# controller_v1.net
KiCad netlist of a schematic drawn in EAGLE
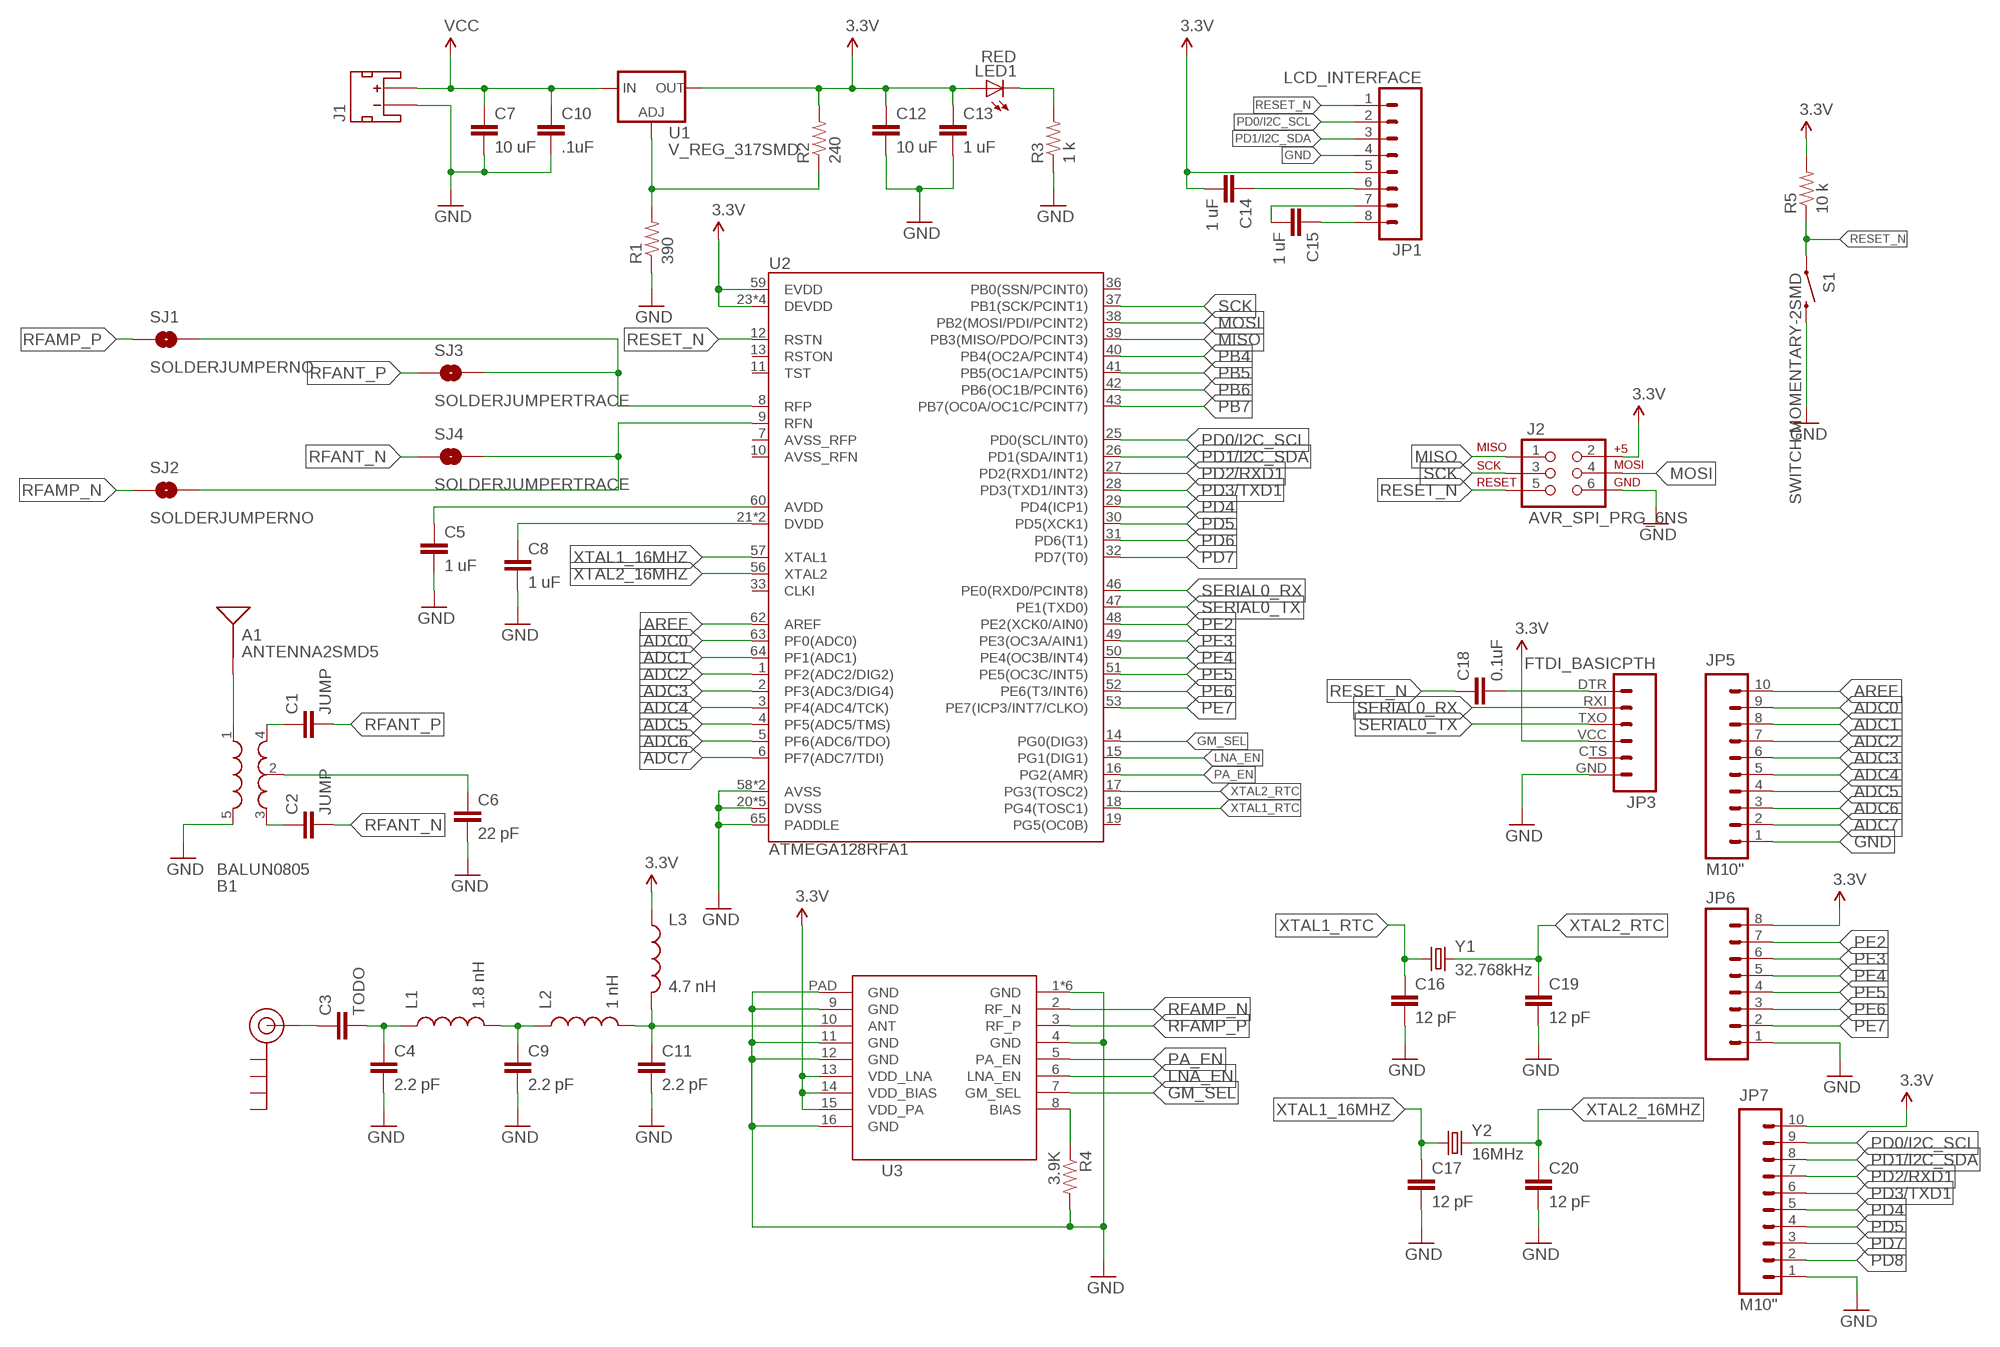
[diagram p0: schematic, sheet 1]

(export (version "E")
  (design (tool "Eeschema 10.0.6"))
  (components
    (comp (ref "A1")
      (value "ANTENNA2SMD5")
      (footprint "eagle-import:ANTENNA-CHIP5")
      (libsource (lib "eagle-import") (part "ANTENNA2SMD5"))
    )
    (comp (ref "B1")
      (value "BALUN0805")
      (footprint "eagle-import:BALUN")
      (libsource (lib "eagle-import") (part "BALUN0805"))
    )
    (comp (ref "C1")
      (value "JUMP")
      (footprint "eagle-import:0805")
      (libsource (lib "eagle-import") (part "Controller_CAP0805"))
    )
    (comp (ref "C2")
      (value "JUMP")
      (footprint "eagle-import:0805")
      (libsource (lib "eagle-import") (part "Controller_CAP0805"))
    )
    (comp (ref "C3")
      (value "TODO")
      (footprint "eagle-import:0805")
      (libsource (lib "eagle-import") (part "Controller_CAP0805"))
    )
    (comp (ref "C4")
      (value "2.2 pF")
      (footprint "eagle-import:0805")
      (libsource (lib "eagle-import") (part "Controller_CAP0805"))
    )
    (comp (ref "C5")
      (value "1 uF")
      (footprint "eagle-import:0805")
      (libsource (lib "eagle-import") (part "Controller_CAP0805"))
    )
    (comp (ref "C6")
      (value "22 pF")
      (footprint "eagle-import:0805")
      (libsource (lib "eagle-import") (part "Controller_CAP0805"))
    )
    (comp (ref "C7")
      (value "10 uF")
      (footprint "eagle-import:0805")
      (libsource (lib "eagle-import") (part "CAP0805"))
    )
    (comp (ref "C8")
      (value "1 uF")
      (footprint "eagle-import:0805")
      (libsource (lib "eagle-import") (part "Controller_CAP0805"))
    )
    (comp (ref "C9")
      (value "2.2 pF")
      (footprint "eagle-import:0805")
      (libsource (lib "eagle-import") (part "Controller_CAP0805"))
    )
    (comp (ref "C10")
      (value ".1uF")
      (footprint "eagle-import:0805")
      (libsource (lib "eagle-import") (part "CAP0805"))
    )
    (comp (ref "C11")
      (value "2.2 pF")
      (footprint "eagle-import:0805")
      (libsource (lib "eagle-import") (part "Controller_CAP0805"))
    )
    (comp (ref "C12")
      (value "10 uF")
      (footprint "eagle-import:0805")
      (libsource (lib "eagle-import") (part "CAP0805"))
    )
    (comp (ref "C13")
      (value "1 uF")
      (footprint "eagle-import:0805")
      (libsource (lib "eagle-import") (part "CAP0805"))
    )
    (comp (ref "C14")
      (value "1 uF")
      (footprint "eagle-import:0805")
      (libsource (lib "eagle-import") (part "Controller_CAP0805"))
    )
    (comp (ref "C15")
      (value "1 uF")
      (footprint "eagle-import:0805")
      (libsource (lib "eagle-import") (part "Controller_CAP0805"))
    )
    (comp (ref "C16")
      (value "12 pF")
      (footprint "eagle-import:0805")
      (libsource (lib "eagle-import") (part "Controller_CAP0805"))
    )
    (comp (ref "C17")
      (value "12 pF")
      (footprint "eagle-import:0805")
      (libsource (lib "eagle-import") (part "Controller_CAP0805"))
    )
    (comp (ref "C18")
      (value "0.1uF")
      (footprint "eagle-import:0805")
      (libsource (lib "eagle-import") (part "Controller_CAP0805"))
    )
    (comp (ref "C19")
      (value "12 pF")
      (footprint "eagle-import:0805")
      (libsource (lib "eagle-import") (part "Controller_CAP0805"))
    )
    (comp (ref "C20")
      (value "12 pF")
      (footprint "eagle-import:0805")
      (libsource (lib "eagle-import") (part "Controller_CAP0805"))
    )
    (comp (ref "J$1")
      (value "SMA_EDGE")
      (footprint "eagle-import:SMA-EDGE")
      (libsource (lib "eagle-import") (part "SMA_EDGE"))
    )
    (comp (ref "J1")
      (value "BATT")
      (footprint "eagle-import:JST-2-SMD")
      (libsource (lib "eagle-import") (part "JST_2MM_MALE"))
    )
    (comp (ref "J2")
      (value "AVR_SPI_PRG_6NS")
      (footprint "eagle-import:2X3-NS")
      (libsource (lib "eagle-import") (part "AVR_SPI_PRG_6NS"))
    )
    (comp (ref "JP1")
      (value "LCD_INTERFACE")
      (footprint "eagle-import:1X08")
      (libsource (lib "eagle-import") (part "M081X08"))
    )
    (comp (ref "JP3")
      (value "FTDI_BASICPTH")
      (footprint "eagle-import:FTDI_BASIC")
      (libsource (lib "eagle-import") (part "FTDI_BASICPTH"))
    )
    (comp (ref "JP5")
      (value "M10\"")
      (footprint "eagle-import:1X10")
      (libsource (lib "eagle-import") (part "M10{dblquote}"))
    )
    (comp (ref "JP6")
      (value "M081X08")
      (footprint "eagle-import:1X08")
      (libsource (lib "eagle-import") (part "M081X08"))
    )
    (comp (ref "JP7")
      (value "M10\"")
      (footprint "eagle-import:1X10")
      (libsource (lib "eagle-import") (part "M10{dblquote}"))
    )
    (comp (ref "L1")
      (value "1.8 nH")
      (footprint "eagle-import:0805")
      (libsource (lib "eagle-import") (part "INDUCTOR0805"))
    )
    (comp (ref "L2")
      (value "1 nH")
      (footprint "eagle-import:0805")
      (libsource (lib "eagle-import") (part "INDUCTOR0805"))
    )
    (comp (ref "L3")
      (value "4.7 nH")
      (footprint "eagle-import:0805")
      (libsource (lib "eagle-import") (part "INDUCTOR0805"))
    )
    (comp (ref "LED1")
      (value "RED")
      (footprint "eagle-import:LED-0603")
      (libsource (lib "eagle-import") (part "LED0603"))
    )
    (comp (ref "R1")
      (value "390")
      (footprint "eagle-import:0805")
      (libsource (lib "eagle-import") (part "RESISTOR0805-RES"))
    )
    (comp (ref "R2")
      (value "240")
      (footprint "eagle-import:0805")
      (libsource (lib "eagle-import") (part "RESISTOR0805-RES"))
    )
    (comp (ref "R3")
      (value "1 k")
      (footprint "eagle-import:0805")
      (libsource (lib "eagle-import") (part "Controller_RESISTOR0805-RES"))
    )
    (comp (ref "R4")
      (value "3.9K")
      (footprint "eagle-import:0805")
      (libsource (lib "eagle-import") (part "Controller_RESISTOR0805-RES"))
    )
    (comp (ref "R5")
      (value "10 k")
      (footprint "eagle-import:0805")
      (libsource (lib "eagle-import") (part "Controller_RESISTOR0805-RES"))
    )
    (comp (ref "S1")
      (value "SWITCH-MOMENTARY-2SMD")
      (footprint "eagle-import:TACTILE_SWITCH_SMD")
      (libsource (lib "eagle-import") (part "SWITCH-MOMENTARY-2SMD"))
    )
    (comp (ref "SJ1")
      (value "SOLDERJUMPERNO")
      (footprint "eagle-import:SJ_2S-NO")
      (libsource (lib "eagle-import") (part "SOLDERJUMPERNO"))
    )
    (comp (ref "SJ2")
      (value "SOLDERJUMPERNO")
      (footprint "eagle-import:SJ_2S-NO")
      (libsource (lib "eagle-import") (part "SOLDERJUMPERNO"))
    )
    (comp (ref "SJ3")
      (value "SOLDERJUMPERTRACE")
      (footprint "eagle-import:SJ_2S-TRACE")
      (libsource (lib "eagle-import") (part "SOLDERJUMPERTRACE"))
    )
    (comp (ref "SJ4")
      (value "SOLDERJUMPERTRACE")
      (footprint "eagle-import:SJ_2S-TRACE")
      (libsource (lib "eagle-import") (part "SOLDERJUMPERTRACE"))
    )
    (comp (ref "U1")
      (value "V_REG_317SMD")
      (footprint "eagle-import:SOT223")
      (libsource (lib "eagle-import") (part "V_REG_317SMD"))
    )
    (comp (ref "U2")
      (value "ATMEGA128RFA1")
      (footprint "eagle-import:QFN-64")
      (libsource (lib "eagle-import") (part "ATMEGA128RFA1"))
    )
    (comp (ref "U3")
      (value "RF_AMPLIFIER")
      (footprint "eagle-import:QFN65P400X400X100-17N")
      (libsource (lib "eagle-import") (part "CC2592QF"))
    )
    (comp (ref "Y1")
      (value "32.768kHz")
      (footprint "eagle-import:CRYSTAL-32KHZ-SMD")
      (libsource (lib "eagle-import") (part "CRYSTAL32-SMD"))
    )
    (comp (ref "Y2")
      (value "16MHz")
      (footprint "eagle-import:CRYSTAL-SMD-5X3")
      (libsource (lib "eagle-import") (part "CRYSTAL5X3"))
    )
  )
  (nets
    (net (code "1") (name "3.3V") (class "Default")
      (node (ref "C12") (pin "1") (pinfunction "1_1") (pintype "passive"))
      (node (ref "C13") (pin "1") (pinfunction "1_1") (pintype "passive"))
      (node (ref "C14") (pin "2") (pinfunction "2_2") (pintype "passive"))
      (node (ref "J2") (pin "2") (pinfunction "2_2") (pintype "passive"))
      (node (ref "JP1") (pin "5") (pinfunction "5_5") (pintype "passive"))
      (node (ref "JP3") (pin "VCC") (pinfunction "4_VCC") (pintype "passive"))
      (node (ref "JP6") (pin "8") (pinfunction "8_8") (pintype "passive"))
      (node (ref "JP7") (pin "10") (pinfunction "10_10") (pintype "passive"))
      (node (ref "L3") (pin "1") (pinfunction "1_1") (pintype "passive"))
      (node (ref "LED1") (pin "A") (pinfunction "A_A") (pintype "passive"))
      (node (ref "R2") (pin "2") (pinfunction "2_2") (pintype "passive"))
      (node (ref "R5") (pin "2") (pinfunction "2_2") (pintype "passive"))
      (node (ref "U1") (pin "2") (pinfunction "OUT_2") (pintype "output"))
      (node (ref "U2") (pin "23") (pinfunction "DEVDD_23") (pintype "bidirectional"))
      (node (ref "U2") (pin "34") (pinfunction "DEVDD_34") (pintype "bidirectional"))
      (node (ref "U2") (pin "44") (pinfunction "DEVDD_44") (pintype "bidirectional"))
      (node (ref "U2") (pin "54") (pinfunction "DEVDD_54") (pintype "bidirectional"))
      (node (ref "U2") (pin "59") (pinfunction "EVDD_59") (pintype "bidirectional"))
      (node (ref "U3") (pin "13") (pinfunction "VDD_LNA_13") (pintype "power_in"))
      (node (ref "U3") (pin "14") (pinfunction "VDD_BIAS_14") (pintype "power_in"))
      (node (ref "U3") (pin "15") (pinfunction "VDD_PA_15") (pintype "power_in"))
    )
    (net (code "2") (name "ADC0") (class "Default")
      (node (ref "JP5") (pin "9") (pinfunction "9_9") (pintype "passive"))
      (node (ref "U2") (pin "63") (pinfunction "PF0(ADC0)_63") (pintype "bidirectional"))
    )
    (net (code "3") (name "ADC1") (class "Default")
      (node (ref "JP5") (pin "8") (pinfunction "8_8") (pintype "passive"))
      (node (ref "U2") (pin "64") (pinfunction "PF1(ADC1)_64") (pintype "bidirectional"))
    )
    (net (code "4") (name "ADC2") (class "Default")
      (node (ref "JP5") (pin "7") (pinfunction "7_7") (pintype "passive"))
      (node (ref "U2") (pin "1") (pinfunction "PF2(ADC2/DIG2)_1") (pintype "bidirectional"))
    )
    (net (code "5") (name "ADC3") (class "Default")
      (node (ref "JP5") (pin "6") (pinfunction "6_6") (pintype "passive"))
      (node (ref "U2") (pin "2") (pinfunction "PF3(ADC3/DIG4)_2") (pintype "bidirectional"))
    )
    (net (code "6") (name "ADC4") (class "Default")
      (node (ref "JP5") (pin "5") (pinfunction "5_5") (pintype "passive"))
      (node (ref "U2") (pin "3") (pinfunction "PF4(ADC4/TCK)_3") (pintype "bidirectional"))
    )
    (net (code "7") (name "ADC5") (class "Default")
      (node (ref "JP5") (pin "4") (pinfunction "4_4") (pintype "passive"))
      (node (ref "U2") (pin "4") (pinfunction "PF5(ADC5/TMS)_4") (pintype "bidirectional"))
    )
    (net (code "8") (name "ADC6") (class "Default")
      (node (ref "JP5") (pin "3") (pinfunction "3_3") (pintype "passive"))
      (node (ref "U2") (pin "5") (pinfunction "PF6(ADC6/TDO)_5") (pintype "bidirectional"))
    )
    (net (code "9") (name "ADC7") (class "Default")
      (node (ref "JP5") (pin "2") (pinfunction "2_2") (pintype "passive"))
      (node (ref "U2") (pin "6") (pinfunction "PF7(ADC7/TDI)_6") (pintype "bidirectional"))
    )
    (net (code "10") (name "AREF") (class "Default")
      (node (ref "JP5") (pin "10") (pinfunction "10_10") (pintype "passive"))
      (node (ref "U2") (pin "62") (pinfunction "AREF_62") (pintype "bidirectional"))
    )
    (net (code "11") (name "GM_SEL") (class "Default")
      (node (ref "U2") (pin "14") (pinfunction "PG0(DIG3)_14") (pintype "bidirectional"))
      (node (ref "U3") (pin "7") (pinfunction "GM_SEL_7") (pintype "input"))
    )
    (net (code "12") (name "GND") (class "Default")
      (node (ref "B1") (pin "5") (pinfunction "GND_5") (pintype "bidirectional"))
      (node (ref "C10") (pin "2") (pinfunction "2_2") (pintype "passive"))
      (node (ref "C11") (pin "2") (pinfunction "2_2") (pintype "passive"))
      (node (ref "C12") (pin "2") (pinfunction "2_2") (pintype "passive"))
      (node (ref "C13") (pin "2") (pinfunction "2_2") (pintype "passive"))
      (node (ref "C16") (pin "2") (pinfunction "2_2") (pintype "passive"))
      (node (ref "C17") (pin "2") (pinfunction "2_2") (pintype "passive"))
      (node (ref "C19") (pin "2") (pinfunction "2_2") (pintype "passive"))
      (node (ref "C20") (pin "2") (pinfunction "2_2") (pintype "passive"))
      (node (ref "C4") (pin "2") (pinfunction "2_2") (pintype "passive"))
      (node (ref "C5") (pin "2") (pinfunction "2_2") (pintype "passive"))
      (node (ref "C6") (pin "2") (pinfunction "2_2") (pintype "passive"))
      (node (ref "C7") (pin "2") (pinfunction "2_2") (pintype "passive"))
      (node (ref "C8") (pin "2") (pinfunction "2_2") (pintype "passive"))
      (node (ref "C9") (pin "2") (pinfunction "2_2") (pintype "passive"))
      (node (ref "J1") (pin "1") (pinfunction "-_1") (pintype "bidirectional"))
      (node (ref "J2") (pin "6") (pinfunction "6_6") (pintype "passive"))
      (node (ref "JP1") (pin "4") (pinfunction "4_4") (pintype "passive"))
      (node (ref "JP3") (pin "GND") (pinfunction "6_GND") (pintype "passive"))
      (node (ref "JP5") (pin "1") (pinfunction "1_1") (pintype "passive"))
      (node (ref "JP6") (pin "1") (pinfunction "1_1") (pintype "passive"))
      (node (ref "JP7") (pin "1") (pinfunction "1_1") (pintype "passive"))
      (node (ref "R1") (pin "1") (pinfunction "1_1") (pintype "passive"))
      (node (ref "R3") (pin "1") (pinfunction "1_1") (pintype "passive"))
      (node (ref "R4") (pin "2") (pinfunction "2_2") (pintype "passive"))
      (node (ref "S1") (pin "3") (pinfunction "2_3") (pintype "passive"))
      (node (ref "U2") (pin "20") (pinfunction "DVSS_20") (pintype "bidirectional"))
      (node (ref "U2") (pin "24") (pinfunction "DVSS_24") (pintype "bidirectional"))
      (node (ref "U2") (pin "35") (pinfunction "DVSS_35") (pintype "bidirectional"))
      (node (ref "U2") (pin "45") (pinfunction "DVSS_45") (pintype "bidirectional"))
      (node (ref "U2") (pin "55") (pinfunction "DVSS_55") (pintype "bidirectional"))
      (node (ref "U2") (pin "58") (pinfunction "AVSS_58") (pintype "bidirectional"))
      (node (ref "U2") (pin "61") (pinfunction "AVSS_61") (pintype "bidirectional"))
      (node (ref "U2") (pin "65") (pinfunction "PADDLE_65") (pintype "bidirectional"))
      (node (ref "U3") (pin "1") (pinfunction "GND_1") (pintype "power_in"))
      (node (ref "U3") (pin "11") (pinfunction "GND_11") (pintype "power_in"))
      (node (ref "U3") (pin "12") (pinfunction "GND_12") (pintype "power_in"))
      (node (ref "U3") (pin "16") (pinfunction "GND_16") (pintype "power_in"))
      (node (ref "U3") (pin "4") (pinfunction "GND_4") (pintype "power_in"))
      (node (ref "U3") (pin "9") (pinfunction "GND_9") (pintype "power_in"))
      (node (ref "U3") (pin "P$1") (pinfunction "GND_P$1") (pintype "power_in"))
      (node (ref "U3") (pin "P$2") (pinfunction "GND_P$2") (pintype "power_in"))
      (node (ref "U3") (pin "P$3") (pinfunction "GND_P$3") (pintype "power_in"))
      (node (ref "U3") (pin "P$4") (pinfunction "GND_P$4") (pintype "power_in"))
      (node (ref "U3") (pin "P$5") (pinfunction "GND_P$5") (pintype "power_in"))
      (node (ref "U3") (pin "PAD") (pinfunction "GND_PAD") (pintype "power_in"))
    )
    (net (code "13") (name "LNA_EN") (class "Default")
      (node (ref "U2") (pin "15") (pinfunction "PG1(DIG1)_15") (pintype "bidirectional"))
      (node (ref "U3") (pin "6") (pinfunction "LNA_EN_6") (pintype "input"))
    )
    (net (code "14") (name "MISO") (class "Default")
      (node (ref "J2") (pin "1") (pinfunction "1_1") (pintype "passive"))
      (node (ref "U2") (pin "39") (pinfunction "PB3(MISO/PDO/PCINT3)_39") (pintype "bidirectional"))
    )
    (net (code "15") (name "MOSI") (class "Default")
      (node (ref "J2") (pin "4") (pinfunction "4_4") (pintype "passive"))
      (node (ref "U2") (pin "38") (pinfunction "PB2(MOSI/PDI/PCINT2)_38") (pintype "bidirectional"))
    )
    (net (code "16") (name "Net-(A1-SIGNAL)") (class "Default")
      (node (ref "A1") (pin "FEED") (pinfunction "SIGNAL_FEED") (pintype "bidirectional"))
      (node (ref "B1") (pin "1") (pinfunction "IN_1") (pintype "bidirectional"))
    )
    (net (code "17") (name "Net-(B1-GND-Pad2)") (class "Default")
      (node (ref "B1") (pin "2") (pinfunction "GND_2") (pintype "bidirectional"))
      (node (ref "C6") (pin "1") (pinfunction "1_1") (pintype "passive"))
    )
    (net (code "18") (name "Net-(B1-OUT1)") (class "Default")
      (node (ref "B1") (pin "4") (pinfunction "OUT1_4") (pintype "bidirectional"))
      (node (ref "C1") (pin "1") (pinfunction "1_1") (pintype "passive"))
    )
    (net (code "19") (name "Net-(B1-OUT2)") (class "Default")
      (node (ref "B1") (pin "3") (pinfunction "OUT2_3") (pintype "bidirectional"))
      (node (ref "C2") (pin "1") (pinfunction "1_1") (pintype "passive"))
    )
    (net (code "20") (name "Net-(C3-Pad2)") (class "Default")
      (node (ref "C3") (pin "2") (pinfunction "2_2") (pintype "passive"))
      (node (ref "C4") (pin "1") (pinfunction "1_1") (pintype "passive"))
      (node (ref "L1") (pin "1") (pinfunction "1_1") (pintype "passive"))
    )
    (net (code "21") (name "Net-(C8-Pad1)") (class "Default")
      (node (ref "C8") (pin "1") (pinfunction "1_1") (pintype "passive"))
      (node (ref "U2") (pin "21") (pinfunction "DVDD_21") (pintype "bidirectional"))
      (node (ref "U2") (pin "22") (pinfunction "DVDD_22") (pintype "bidirectional"))
    )
    (net (code "22") (name "Net-(C9-Pad1)") (class "Default")
      (node (ref "C9") (pin "1") (pinfunction "1_1") (pintype "passive"))
      (node (ref "L1") (pin "2") (pinfunction "2_2") (pintype "passive"))
      (node (ref "L2") (pin "1") (pinfunction "1_1") (pintype "passive"))
    )
    (net (code "23") (name "Net-(C14-Pad1)") (class "Default")
      (node (ref "C14") (pin "1") (pinfunction "1_1") (pintype "passive"))
      (node (ref "JP1") (pin "6") (pinfunction "6_6") (pintype "passive"))
    )
    (net (code "24") (name "Net-(C15-Pad1)") (class "Default")
      (node (ref "C15") (pin "1") (pinfunction "1_1") (pintype "passive"))
      (node (ref "JP1") (pin "8") (pinfunction "8_8") (pintype "passive"))
    )
    (net (code "25") (name "Net-(C15-Pad2)") (class "Default")
      (node (ref "C15") (pin "2") (pinfunction "2_2") (pintype "passive"))
      (node (ref "JP1") (pin "7") (pinfunction "7_7") (pintype "passive"))
    )
    (net (code "26") (name "Net-(J$1-SIGNAL)") (class "Default")
      (node (ref "C3") (pin "1") (pinfunction "1_1") (pintype "passive"))
      (node (ref "J$1") (pin "SIG") (pinfunction "SIGNAL_SIG") (pintype "bidirectional"))
    )
    (net (code "27") (name "Net-(JP3-1)") (class "Default")
      (node (ref "C18") (pin "2") (pinfunction "2_2") (pintype "passive"))
      (node (ref "JP3") (pin "DTR") (pinfunction "1_DTR") (pintype "passive"))
    )
    (net (code "28") (name "Net-(LED1-PadC)") (class "Default")
      (node (ref "LED1") (pin "C") (pinfunction "C_C") (pintype "passive"))
      (node (ref "R3") (pin "2") (pinfunction "2_2") (pintype "passive"))
    )
    (net (code "29") (name "Net-(U1-ADJ)") (class "Default")
      (node (ref "R1") (pin "2") (pinfunction "2_2") (pintype "passive"))
      (node (ref "R2") (pin "1") (pinfunction "1_1") (pintype "passive"))
      (node (ref "U1") (pin "1") (pinfunction "ADJ_1") (pintype "input"))
    )
    (net (code "30") (name "Net-(U2-AVDD)") (class "Default")
      (node (ref "C5") (pin "1") (pinfunction "1_1") (pintype "passive"))
      (node (ref "U2") (pin "60") (pinfunction "AVDD_60") (pintype "bidirectional"))
    )
    (net (code "31") (name "Net-(U2-RFN)") (class "Default")
      (node (ref "SJ2") (pin "2") (pinfunction "2_2") (pintype "passive"))
      (node (ref "SJ4") (pin "2") (pinfunction "2_2") (pintype "passive"))
      (node (ref "U2") (pin "9") (pinfunction "RFN_9") (pintype "bidirectional"))
    )
    (net (code "32") (name "Net-(U2-RFP)") (class "Default")
      (node (ref "SJ1") (pin "2") (pinfunction "2_2") (pintype "passive"))
      (node (ref "SJ3") (pin "2") (pinfunction "2_2") (pintype "passive"))
      (node (ref "U2") (pin "8") (pinfunction "RFP_8") (pintype "bidirectional"))
    )
    (net (code "33") (name "Net-(U3-ANT)") (class "Default")
      (node (ref "C11") (pin "1") (pinfunction "1_1") (pintype "passive"))
      (node (ref "L2") (pin "2") (pinfunction "2_2") (pintype "passive"))
      (node (ref "L3") (pin "2") (pinfunction "2_2") (pintype "passive"))
      (node (ref "U3") (pin "10") (pinfunction "ANT_10") (pintype "bidirectional"))
    )
    (net (code "34") (name "Net-(U3-BIAS)") (class "Default")
      (node (ref "R4") (pin "1") (pinfunction "1_1") (pintype "passive"))
      (node (ref "U3") (pin "8") (pinfunction "BIAS_8") (pintype "passive"))
    )
    (net (code "35") (name "PA_EN") (class "Default")
      (node (ref "U2") (pin "16") (pinfunction "PG2(AMR)_16") (pintype "bidirectional"))
      (node (ref "U3") (pin "5") (pinfunction "PA_EN_5") (pintype "input"))
    )
    (net (code "36") (name "PB4") (class "Default")
      (node (ref "U2") (pin "40") (pinfunction "PB4(OC2A/PCINT4)_40") (pintype "bidirectional"))
    )
    (net (code "37") (name "PB5") (class "Default")
      (node (ref "U2") (pin "41") (pinfunction "PB5(OC1A/PCINT5)_41") (pintype "bidirectional"))
    )
    (net (code "38") (name "PB6") (class "Default")
      (node (ref "U2") (pin "42") (pinfunction "PB6(OC1B/PCINT6)_42") (pintype "bidirectional"))
    )
    (net (code "39") (name "PB7") (class "Default")
      (node (ref "U2") (pin "43") (pinfunction "PB7(OC0A/OC1C/PCINT7)_43") (pintype "bidirectional"))
    )
    (net (code "40") (name "PD0{slash}I2C_SCL") (class "Default")
      (node (ref "JP1") (pin "2") (pinfunction "2_2") (pintype "passive"))
      (node (ref "JP7") (pin "9") (pinfunction "9_9") (pintype "passive"))
      (node (ref "U2") (pin "25") (pinfunction "PD0(SCL/INT0)_25") (pintype "bidirectional"))
    )
    (net (code "41") (name "PD1{slash}I2C_SDA") (class "Default")
      (node (ref "JP1") (pin "3") (pinfunction "3_3") (pintype "passive"))
      (node (ref "JP7") (pin "8") (pinfunction "8_8") (pintype "passive"))
      (node (ref "U2") (pin "26") (pinfunction "PD1(SDA/INT1)_26") (pintype "bidirectional"))
    )
    (net (code "42") (name "PD2{slash}RXD1") (class "Default")
      (node (ref "JP7") (pin "7") (pinfunction "7_7") (pintype "passive"))
      (node (ref "U2") (pin "27") (pinfunction "PD2(RXD1/INT2)_27") (pintype "bidirectional"))
    )
    (net (code "43") (name "PD3{slash}TXD1") (class "Default")
      (node (ref "JP7") (pin "6") (pinfunction "6_6") (pintype "passive"))
      (node (ref "U2") (pin "28") (pinfunction "PD3(TXD1/INT3)_28") (pintype "bidirectional"))
    )
    (net (code "44") (name "PD4") (class "Default")
      (node (ref "JP7") (pin "5") (pinfunction "5_5") (pintype "passive"))
      (node (ref "U2") (pin "29") (pinfunction "PD4(ICP1)_29") (pintype "bidirectional"))
    )
    (net (code "45") (name "PD5") (class "Default")
      (node (ref "JP7") (pin "4") (pinfunction "4_4") (pintype "passive"))
      (node (ref "U2") (pin "30") (pinfunction "PD5(XCK1)_30") (pintype "bidirectional"))
    )
    (net (code "46") (name "PD6") (class "Default")
      (node (ref "U2") (pin "31") (pinfunction "PD6(T1)_31") (pintype "bidirectional"))
    )
    (net (code "47") (name "PD7") (class "Default")
      (node (ref "JP7") (pin "3") (pinfunction "3_3") (pintype "passive"))
      (node (ref "U2") (pin "32") (pinfunction "PD7(T0)_32") (pintype "bidirectional"))
    )
    (net (code "48") (name "PD8") (class "Default")
      (node (ref "JP7") (pin "2") (pinfunction "2_2") (pintype "passive"))
    )
    (net (code "49") (name "PE2") (class "Default")
      (node (ref "JP6") (pin "7") (pinfunction "7_7") (pintype "passive"))
      (node (ref "U2") (pin "48") (pinfunction "PE2(XCK0/AIN0)_48") (pintype "bidirectional"))
    )
    (net (code "50") (name "PE3") (class "Default")
      (node (ref "JP6") (pin "6") (pinfunction "6_6") (pintype "passive"))
      (node (ref "U2") (pin "49") (pinfunction "PE3(OC3A/AIN1)_49") (pintype "bidirectional"))
    )
    (net (code "51") (name "PE4") (class "Default")
      (node (ref "JP6") (pin "5") (pinfunction "5_5") (pintype "passive"))
      (node (ref "U2") (pin "50") (pinfunction "PE4(OC3B/INT4)_50") (pintype "bidirectional"))
    )
    (net (code "52") (name "PE5") (class "Default")
      (node (ref "JP6") (pin "4") (pinfunction "4_4") (pintype "passive"))
      (node (ref "U2") (pin "51") (pinfunction "PE5(OC3C/INT5)_51") (pintype "bidirectional"))
    )
    (net (code "53") (name "PE6") (class "Default")
      (node (ref "JP6") (pin "3") (pinfunction "3_3") (pintype "passive"))
      (node (ref "U2") (pin "52") (pinfunction "PE6(T3/INT6)_52") (pintype "bidirectional"))
    )
    (net (code "54") (name "PE7") (class "Default")
      (node (ref "JP6") (pin "2") (pinfunction "2_2") (pintype "passive"))
      (node (ref "U2") (pin "53") (pinfunction "PE7(ICP3/INT7/CLKO)_53") (pintype "bidirectional"))
    )
    (net (code "55") (name "RESET_N") (class "Default")
      (node (ref "C18") (pin "1") (pinfunction "1_1") (pintype "passive"))
      (node (ref "J2") (pin "5") (pinfunction "5_5") (pintype "passive"))
      (node (ref "JP1") (pin "1") (pinfunction "1_1") (pintype "passive"))
      (node (ref "R5") (pin "1") (pinfunction "1_1") (pintype "passive"))
      (node (ref "S1") (pin "1") (pinfunction "1_1") (pintype "passive"))
      (node (ref "U2") (pin "12") (pinfunction "RSTN_12") (pintype "bidirectional"))
    )
    (net (code "56") (name "RFAMP_N") (class "Default")
      (node (ref "SJ2") (pin "1") (pinfunction "1_1") (pintype "passive"))
      (node (ref "U3") (pin "2") (pinfunction "RF_N_2") (pintype "bidirectional"))
    )
    (net (code "57") (name "RFAMP_P") (class "Default")
      (node (ref "SJ1") (pin "1") (pinfunction "1_1") (pintype "passive"))
      (node (ref "U3") (pin "3") (pinfunction "RF_P_3") (pintype "bidirectional"))
    )
    (net (code "58") (name "RFANT_N") (class "Default")
      (node (ref "C2") (pin "2") (pinfunction "2_2") (pintype "passive"))
      (node (ref "SJ4") (pin "1") (pinfunction "1_1") (pintype "passive"))
    )
    (net (code "59") (name "RFANT_P") (class "Default")
      (node (ref "C1") (pin "2") (pinfunction "2_2") (pintype "passive"))
      (node (ref "SJ3") (pin "1") (pinfunction "1_1") (pintype "passive"))
    )
    (net (code "60") (name "SCK") (class "Default")
      (node (ref "J2") (pin "3") (pinfunction "3_3") (pintype "passive"))
      (node (ref "U2") (pin "37") (pinfunction "PB1(SCK/PCINT1)_37") (pintype "bidirectional"))
    )
    (net (code "61") (name "SERIAL0_RX") (class "Default")
      (node (ref "JP3") (pin "RXI") (pinfunction "2_RXI") (pintype "passive"))
      (node (ref "U2") (pin "46") (pinfunction "PE0(RXD0/PCINT8)_46") (pintype "bidirectional"))
    )
    (net (code "62") (name "SERIAL0_TX") (class "Default")
      (node (ref "JP3") (pin "TXO") (pinfunction "3_TXO") (pintype "passive"))
      (node (ref "U2") (pin "47") (pinfunction "PE1(TXD0)_47") (pintype "bidirectional"))
    )
    (net (code "63") (name "VCC") (class "Default")
      (node (ref "C10") (pin "1") (pinfunction "1_1") (pintype "passive"))
      (node (ref "C7") (pin "1") (pinfunction "1_1") (pintype "passive"))
      (node (ref "J1") (pin "2") (pinfunction "+_2") (pintype "bidirectional"))
      (node (ref "U1") (pin "3") (pinfunction "IN_3") (pintype "input"))
    )
    (net (code "64") (name "XTAL1_16MHZ") (class "Default")
      (node (ref "C17") (pin "1") (pinfunction "1_1") (pintype "passive"))
      (node (ref "U2") (pin "57") (pinfunction "XTAL1_57") (pintype "bidirectional"))
      (node (ref "Y2") (pin "1") (pinfunction "1_1") (pintype "passive"))
    )
    (net (code "65") (name "XTAL1_RTC") (class "Default")
      (node (ref "C16") (pin "1") (pinfunction "1_1") (pintype "passive"))
      (node (ref "U2") (pin "18") (pinfunction "PG4(TOSC1)_18") (pintype "bidirectional"))
      (node (ref "Y1") (pin "X1") (pinfunction "1_X1") (pintype "passive"))
    )
    (net (code "66") (name "XTAL2_16MHZ") (class "Default")
      (node (ref "C20") (pin "1") (pinfunction "1_1") (pintype "passive"))
      (node (ref "U2") (pin "56") (pinfunction "XTAL2_56") (pintype "bidirectional"))
      (node (ref "Y2") (pin "3") (pinfunction "2_3") (pintype "passive"))
    )
    (net (code "67") (name "XTAL2_RTC") (class "Default")
      (node (ref "C19") (pin "1") (pinfunction "1_1") (pintype "passive"))
      (node (ref "U2") (pin "17") (pinfunction "PG3(TOSC2)_17") (pintype "bidirectional"))
      (node (ref "Y1") (pin "X2") (pinfunction "2_X2") (pintype "passive"))
    )
    (net (code "68") (name "unconnected-(J$1-GND-PadGND@0)") (class "Default")
      (node (ref "J$1") (pin "GND@0") (pinfunction "GND_GND@0") (pintype "bidirectional"))
    )
    (net (code "69") (name "unconnected-(J$1-GND-PadGND@1)") (class "Default")
      (node (ref "J$1") (pin "GND@1") (pinfunction "GND_GND@1") (pintype "bidirectional"))
    )
    (net (code "70") (name "unconnected-(J$1-GND-PadGND@2)") (class "Default")
      (node (ref "J$1") (pin "GND@2") (pinfunction "GND_GND@2") (pintype "bidirectional"))
    )
    (net (code "71") (name "unconnected-(J$1-GND-PadGND@3)") (class "Default")
      (node (ref "J$1") (pin "GND@3") (pinfunction "GND_GND@3") (pintype "bidirectional"))
    )
    (net (code "72") (name "unconnected-(J1-PAD1-PadNC1)") (class "Default")
      (node (ref "J1") (pin "NC1") (pinfunction "PAD1_NC1") (pintype "bidirectional"))
    )
    (net (code "73") (name "unconnected-(J1-PAD2-PadNC2)") (class "Default")
      (node (ref "J1") (pin "NC2") (pinfunction "PAD2_NC2") (pintype "bidirectional"))
    )
    (net (code "74") (name "unconnected-(JP3-5-PadCTS)") (class "Default")
      (node (ref "JP3") (pin "CTS") (pinfunction "5_CTS") (pintype "passive"))
    )
    (net (code "75") (name "unconnected-(U2-AVSS_RFN-Pad10)") (class "Default")
      (node (ref "U2") (pin "10") (pinfunction "AVSS_RFN_10") (pintype "bidirectional"))
    )
    (net (code "76") (name "unconnected-(U2-AVSS_RFP-Pad7)") (class "Default")
      (node (ref "U2") (pin "7") (pinfunction "AVSS_RFP_7") (pintype "bidirectional"))
    )
    (net (code "77") (name "unconnected-(U2-CLKI-Pad33)") (class "Default")
      (node (ref "U2") (pin "33") (pinfunction "CLKI_33") (pintype "bidirectional"))
    )
    (net (code "78") (name "unconnected-(U2-PB0(SSN{slash}PCINT0)-Pad36)") (class "Default")
      (node (ref "U2") (pin "36") (pinfunction "PB0(SSN/PCINT0)_36") (pintype "bidirectional"))
    )
    (net (code "79") (name "unconnected-(U2-PG5(OC0B)-Pad19)") (class "Default")
      (node (ref "U2") (pin "19") (pinfunction "PG5(OC0B)_19") (pintype "bidirectional"))
    )
    (net (code "80") (name "unconnected-(U2-RSTON-Pad13)") (class "Default")
      (node (ref "U2") (pin "13") (pinfunction "RSTON_13") (pintype "bidirectional"))
    )
    (net (code "81") (name "unconnected-(U2-TST-Pad11)") (class "Default")
      (node (ref "U2") (pin "11") (pinfunction "TST_11") (pintype "bidirectional"))
    )
  )
)
